# SPI_IFC.net
KiCad netlist of a schematic drawn in Altium Designer
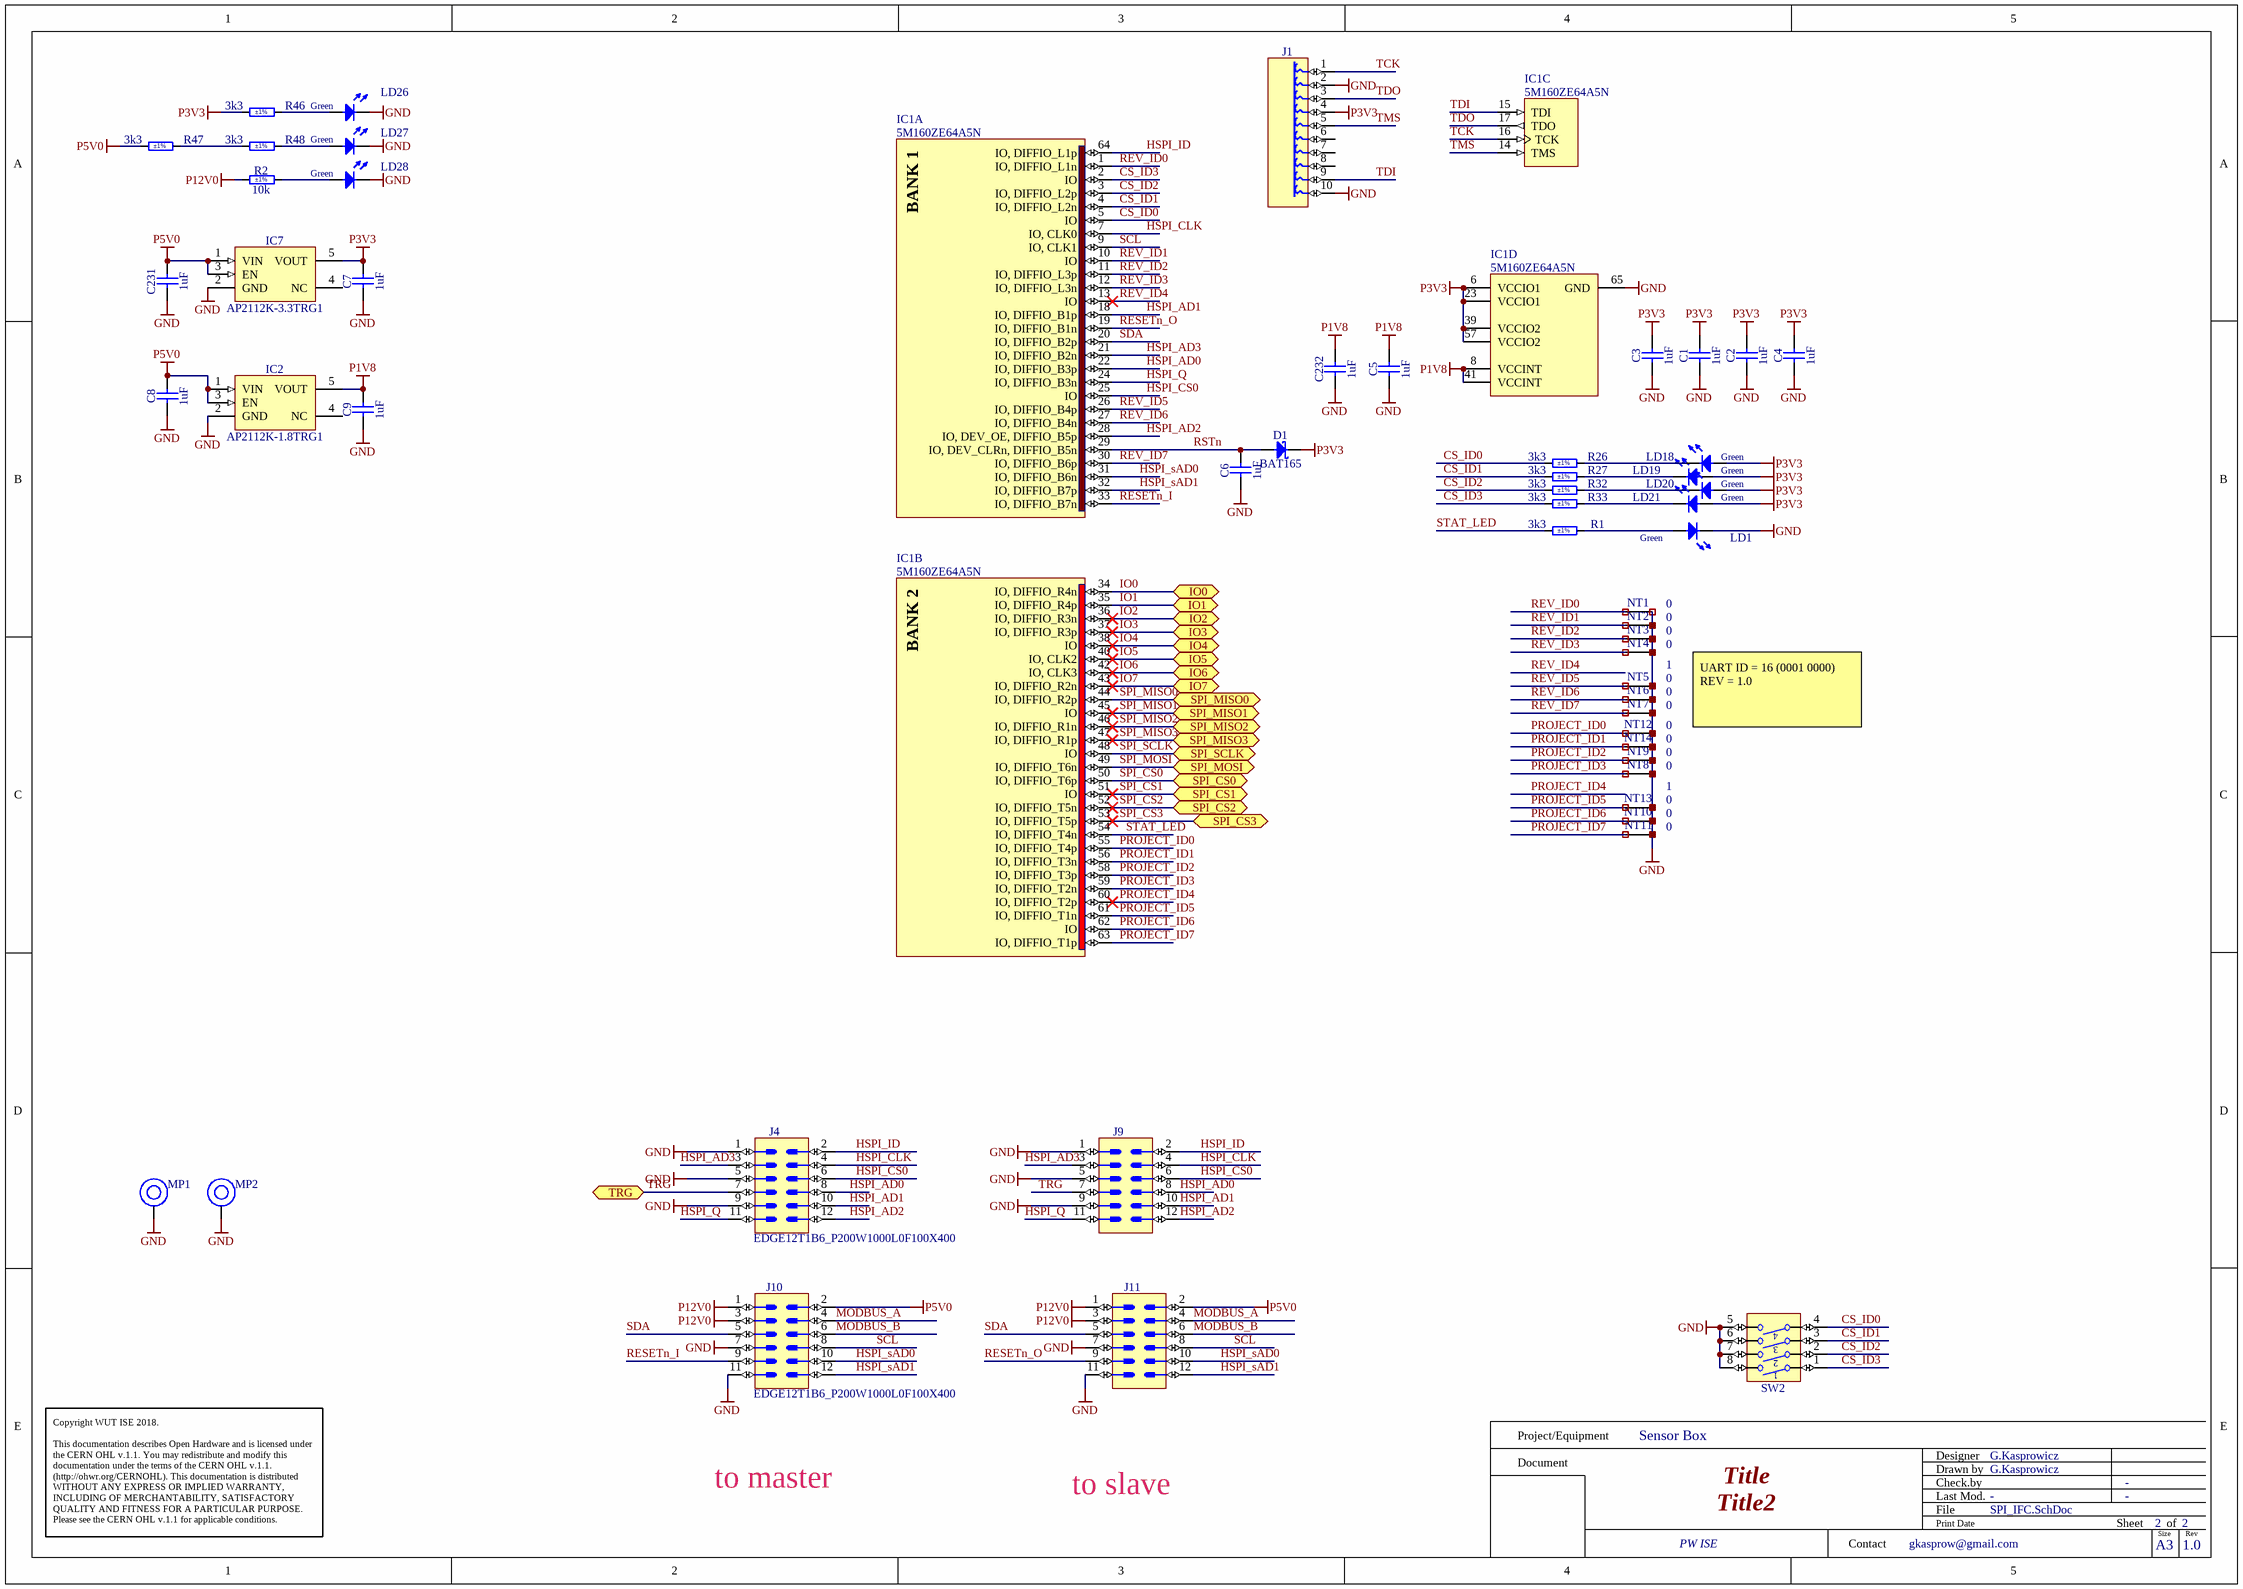
[diagram p0: SPI_IFC.SchDoc]

(export (version "E")
  (design (tool "Eeschema 10.0.6"))
  (components
    (comp (ref "C1")
      (value "1uF")
      (footprint "CAPC1005X55N")
      (description "Non-polarised capacitor")
      (fields
        (field (name "PART NUMBER") "CC0402_1UF_16V_10%_X5R")
        (field (name "VOLTAGE") "16V")
        (field (name "AUTHOR") "CERN DEM JLC")
      )
      (libsource (lib "Capacitors") (part "Capacitor - non polarized"))
    )
    (comp (ref "C2")
      (value "1uF")
      (footprint "CAPC1005X55N")
      (description "Non-polarised capacitor")
      (fields
        (field (name "PART NUMBER") "CC0402_1UF_16V_10%_X5R")
        (field (name "VOLTAGE") "16V")
        (field (name "AUTHOR") "CERN DEM JLC")
      )
      (libsource (lib "Capacitors") (part "Capacitor - non polarized"))
    )
    (comp (ref "C3")
      (value "1uF")
      (footprint "CAPC1005X55N")
      (description "Non-polarised capacitor")
      (fields
        (field (name "PART NUMBER") "CC0402_1UF_16V_10%_X5R")
        (field (name "VOLTAGE") "16V")
        (field (name "AUTHOR") "CERN DEM JLC")
      )
      (libsource (lib "Capacitors") (part "Capacitor - non polarized"))
    )
    (comp (ref "C4")
      (value "1uF")
      (footprint "CAPC1005X55N")
      (description "Non-polarised capacitor")
      (fields
        (field (name "PART NUMBER") "CC0402_1UF_16V_10%_X5R")
        (field (name "VOLTAGE") "16V")
        (field (name "AUTHOR") "CERN DEM JLC")
      )
      (libsource (lib "Capacitors") (part "Capacitor - non polarized"))
    )
    (comp (ref "C5")
      (value "1uF")
      (footprint "CAPC1005X55N")
      (description "Non-polarised capacitor")
      (fields
        (field (name "PART NUMBER") "CC0402_1UF_16V_10%_X5R")
        (field (name "VOLTAGE") "16V")
        (field (name "AUTHOR") "CERN DEM JLC")
      )
      (libsource (lib "Capacitors") (part "Capacitor - non polarized"))
    )
    (comp (ref "C6")
      (value "1uF")
      (footprint "CAPC1005X55N")
      (description "Non-polarised capacitor")
      (fields
        (field (name "PART NUMBER") "CC0402_1UF_16V_10%_X5R")
        (field (name "VOLTAGE") "16V")
        (field (name "AUTHOR") "CERN DEM JLC")
      )
      (libsource (lib "Capacitors") (part "Capacitor - non polarized"))
    )
    (comp (ref "C7")
      (value "1uF")
      (footprint "CAPC1005X55N")
      (description "Non-polarised capacitor")
      (fields
        (field (name "PART NUMBER") "CC0402_1UF_16V_10%_X5R")
        (field (name "VOLTAGE") "16V")
        (field (name "AUTHOR") "CERN DEM JLC")
      )
      (libsource (lib "Capacitors") (part "Capacitor - non polarized"))
    )
    (comp (ref "C8")
      (value "1uF")
      (footprint "CAPC1005X55N")
      (description "Non-polarised capacitor")
      (fields
        (field (name "PART NUMBER") "CC0402_1UF_16V_10%_X5R")
        (field (name "VOLTAGE") "16V")
        (field (name "AUTHOR") "CERN DEM JLC")
      )
      (libsource (lib "Capacitors") (part "Capacitor - non polarized"))
    )
    (comp (ref "C9")
      (value "1uF")
      (footprint "CAPC1005X55N")
      (description "Non-polarised capacitor")
      (fields
        (field (name "PART NUMBER") "CC0402_1UF_16V_10%_X5R")
        (field (name "VOLTAGE") "16V")
        (field (name "AUTHOR") "CERN DEM JLC")
      )
      (libsource (lib "Capacitors") (part "Capacitor - non polarized"))
    )
    (comp (ref "C231")
      (value "1uF")
      (footprint "CAPC1005X55N")
      (description "Non-polarised capacitor")
      (fields
        (field (name "PART NUMBER") "CC0402_1UF_16V_10%_X5R")
        (field (name "VOLTAGE") "16V")
        (field (name "AUTHOR") "CERN DEM JLC")
      )
      (libsource (lib "Capacitors") (part "Capacitor - non polarized"))
    )
    (comp (ref "C232")
      (value "1uF")
      (footprint "CAPC1005X55N")
      (description "Non-polarised capacitor")
      (fields
        (field (name "PART NUMBER") "CC0402_1UF_16V_10%_X5R")
        (field (name "VOLTAGE") "16V")
        (field (name "AUTHOR") "CERN DEM JLC")
      )
      (libsource (lib "Capacitors") (part "Capacitor - non polarized"))
    )
    (comp (ref "D1")
      (value "BAT165")
      (footprint "SOD2512X110N")
      (description "Schottky Diode")
      (fields
        (field (name "VOLTAGE") "40V")
        (field (name "POWER") "750mA")
        (field (name "AUTHOR") "CERN DEM JLC")
      )
      (libsource (lib "ICs And Semiconductors") (part "Diode Schottky"))
    )
    (comp (ref "IC1")
      (value "5M160ZE64A5N")
      (footprint "QFP40P900X900X120-65N-S550")
      (fields (field (name "MANUFACTURER") "ALTERA") (field (name "AUTHOR") "CERN DEM JLC"))
      (libsource (lib "ICs And Semiconductors") (part "5M160ZE64A5N"))
    )
    (comp (ref "IC2")
      (value "AP2112K-1.8TRG1")
      (footprint "SOT95P285X140-5N")
      (description "600mA CMOS Low Dropout Linear Regulator with Enable")
      (fields
        (field (name "MANUFACTURER") "DIODES INCORPORATED")
        (field (name "MANUFACTURER PART NUMBER") "AP2112K-1.8")
        (field (name "AUTHOR") "CERN DEM JLC")
      )
      (libsource (lib "ICs And Semiconductors") (part "AP2112K"))
    )
    (comp (ref "IC7")
      (value "AP2112K-3.3TRG1")
      (footprint "SOT95P285X140-5N")
      (description "600mA CMOS Low Dropout Linear Regulator with Enable")
      (fields
        (field (name "MANUFACTURER") "DIODES INCORPORATED")
        (field (name "MANUFACTURER PART NUMBER") "AP2112K-3.3")
        (field (name "AUTHOR") "CERN DEM MR")
      )
      (libsource (lib "ICs And Semiconductors") (part "AP2112K"))
    )
    (comp (ref "J1")
      (value "TC2050-IDC")
      (footprint "TC2050-IDC")
      (description "TC2030-MCP and TC2050-IDC Pad Contact")
      (fields (field (name "AUTHOR") "CERN DEM HF"))
      (libsource (lib "Eletro-mechanical") (part "TC2050-IDC"))
    )
    (comp (ref "J4")
      (value "~")
      (footprint "EDGE12T1B6_P200W1000L0F100X400")
      (description "PCB Edge Connector 12 (2x6)")
      (fields
        (field (name "PART NUMBER") "EDGE10T1B6_P200W1000L0F100X400")
        (field (name "AUTHOR") "CERN DEM MR")
      )
      (libsource (lib "Connectors") (part "PCB Edge Connector 12 (2x6)"))
    )
    (comp (ref "J9")
      (value "~")
      (footprint "EDGE12T5B10_P200W1000L0F100X400")
      (description "PCB Edge Connector 12 (2x6)")
      (fields (field (name "PART NUMBER") "EDGE12T5B10_P200W1000L0F100X400") (field (name "AUTHOR") "GK"))
      (libsource (lib "Connectors") (part "PCB Edge Connector 12 (2x6) R"))
    )
    (comp (ref "J10")
      (value "~")
      (footprint "EDGE12T1B6_P200W1000L0F100X400")
      (description "PCB Edge Connector 12 (2x6)")
      (fields
        (field (name "PART NUMBER") "EDGE10T1B6_P200W1000L0F100X400")
        (field (name "AUTHOR") "CERN DEM MR")
      )
      (libsource (lib "Connectors") (part "PCB Edge Connector 12 (2x6)"))
    )
    (comp (ref "J11")
      (value "~")
      (footprint "EDGE12T5B10_P200W1000L0F100X400")
      (description "PCB Edge Connector 12 (2x6)")
      (fields (field (name "PART NUMBER") "EDGE12T5B10_P200W1000L0F100X400") (field (name "AUTHOR") "GK"))
      (libsource (lib "Connectors") (part "PCB Edge Connector 12 (2x6) R"))
    )
    (comp (ref "LD1")
      (value "Green")
      (footprint "LED_KINGBRIGHT_KP-1608CGCK")
      (description "LED Green 1C 2A")
      (fields
        (field (name "PART NUMBER") "LED_KINGBRIGHT_KP-1608CGCK")
        (field (name "MANUFACTURER") "KINGBRIGHT")
        (field (name "AUTHOR") "CERN DEM HF")
      )
      (libsource (lib "ICs And Semiconductors") (part "LED Green 1C 2A"))
    )
    (comp (ref "LD18")
      (value "Green")
      (footprint "LED_KINGBRIGHT_KP-1608CGCK")
      (description "LED Green 1C 2A")
      (fields
        (field (name "PART NUMBER") "LED_KINGBRIGHT_KP-1608CGCK")
        (field (name "MANUFACTURER") "KINGBRIGHT")
        (field (name "AUTHOR") "CERN DEM HF")
      )
      (libsource (lib "ICs And Semiconductors") (part "LED Green 1C 2A"))
    )
    (comp (ref "LD19")
      (value "Green")
      (footprint "LED_KINGBRIGHT_KP-1608CGCK")
      (description "LED Green 1C 2A")
      (fields
        (field (name "PART NUMBER") "LED_KINGBRIGHT_KP-1608CGCK")
        (field (name "MANUFACTURER") "KINGBRIGHT")
        (field (name "AUTHOR") "CERN DEM HF")
      )
      (libsource (lib "ICs And Semiconductors") (part "LED Green 1C 2A"))
    )
    (comp (ref "LD20")
      (value "Green")
      (footprint "LED_KINGBRIGHT_KP-1608CGCK")
      (description "LED Green 1C 2A")
      (fields
        (field (name "PART NUMBER") "LED_KINGBRIGHT_KP-1608CGCK")
        (field (name "MANUFACTURER") "KINGBRIGHT")
        (field (name "AUTHOR") "CERN DEM HF")
      )
      (libsource (lib "ICs And Semiconductors") (part "LED Green 1C 2A"))
    )
    (comp (ref "LD21")
      (value "Green")
      (footprint "LED_KINGBRIGHT_KP-1608CGCK")
      (description "LED Green 1C 2A")
      (fields
        (field (name "PART NUMBER") "LED_KINGBRIGHT_KP-1608CGCK")
        (field (name "MANUFACTURER") "KINGBRIGHT")
        (field (name "AUTHOR") "CERN DEM HF")
      )
      (libsource (lib "ICs And Semiconductors") (part "LED Green 1C 2A"))
    )
    (comp (ref "LD26")
      (value "Green")
      (footprint "LED_KINGBRIGHT_KP-1608CGCK")
      (description "LED Green 1C 2A")
      (fields
        (field (name "PART NUMBER") "LED_KINGBRIGHT_KP-1608CGCK")
        (field (name "MANUFACTURER") "KINGBRIGHT")
        (field (name "AUTHOR") "CERN DEM HF")
      )
      (libsource (lib "ICs And Semiconductors") (part "LED Green 1C 2A"))
    )
    (comp (ref "LD27")
      (value "Green")
      (footprint "LED_KINGBRIGHT_KP-1608CGCK")
      (description "LED Green 1C 2A")
      (fields
        (field (name "PART NUMBER") "LED_KINGBRIGHT_KP-1608CGCK")
        (field (name "MANUFACTURER") "KINGBRIGHT")
        (field (name "AUTHOR") "CERN DEM HF")
      )
      (libsource (lib "ICs And Semiconductors") (part "LED Green 1C 2A"))
    )
    (comp (ref "LD28")
      (value "Green")
      (footprint "LED_KINGBRIGHT_KP-1608CGCK")
      (description "LED Green 1C 2A")
      (fields
        (field (name "PART NUMBER") "LED_KINGBRIGHT_KP-1608CGCK")
        (field (name "MANUFACTURER") "KINGBRIGHT")
        (field (name "AUTHOR") "CERN DEM HF")
      )
      (libsource (lib "ICs And Semiconductors") (part "LED Green 1C 2A"))
    )
    (comp (ref "MP1")
      (value "M1.6 x 3mm")
      (footprint "97730306330")
      (description "WA-SMSI SMT Steel Spacer with internal Thread Bottom closed, OD 3.3mm, M1.6 x 3mm")
      (fields
        (field (name "MANUFACTURER PART NUMBER") "97730306330R")
        (field (name "MANUFACTURER") "Wurth Elektronik")
      )
      (libsource (lib "Altium_WA-SMSI (rev22a)") (part "97730306330R"))
    )
    (comp (ref "MP2")
      (value "M1.6 x 3mm")
      (footprint "97730306330")
      (description "WA-SMSI SMT Steel Spacer with internal Thread Bottom closed, OD 3.3mm, M1.6 x 3mm")
      (fields
        (field (name "MANUFACTURER PART NUMBER") "97730306330R")
        (field (name "MANUFACTURER") "Wurth Elektronik")
      )
      (libsource (lib "Altium_WA-SMSI (rev22a)") (part "97730306330R"))
    )
    (comp (ref "NT1")
      (value "Net Tie")
      (footprint "Net Tie 3")
      (fields (field (name "PART NUMBER") "Net Tie 3") (field (name "AUTHOR") "CERN DEM HF"))
      (libsource (lib "Eletro-mechanical") (part "Net Tie_a"))
    )
    (comp (ref "NT2")
      (value "Net Tie")
      (footprint "Net Tie 3")
      (fields (field (name "PART NUMBER") "Net Tie 3") (field (name "AUTHOR") "CERN DEM HF"))
      (libsource (lib "Eletro-mechanical") (part "Net Tie_a"))
    )
    (comp (ref "NT3")
      (value "Net Tie")
      (footprint "Net Tie 3")
      (fields (field (name "PART NUMBER") "Net Tie 3") (field (name "AUTHOR") "CERN DEM HF"))
      (libsource (lib "Eletro-mechanical") (part "Net Tie_a"))
    )
    (comp (ref "NT4")
      (value "Net Tie")
      (footprint "Net Tie 3")
      (fields (field (name "PART NUMBER") "Net Tie 3") (field (name "AUTHOR") "CERN DEM HF"))
      (libsource (lib "Eletro-mechanical") (part "Net Tie_a"))
    )
    (comp (ref "NT5")
      (value "Net Tie")
      (footprint "Net Tie 3")
      (fields (field (name "PART NUMBER") "Net Tie 3") (field (name "AUTHOR") "CERN DEM HF"))
      (libsource (lib "Eletro-mechanical") (part "Net Tie_a"))
    )
    (comp (ref "NT6")
      (value "Net Tie")
      (footprint "Net Tie 3")
      (fields (field (name "PART NUMBER") "Net Tie 3") (field (name "AUTHOR") "CERN DEM HF"))
      (libsource (lib "Eletro-mechanical") (part "Net Tie_a"))
    )
    (comp (ref "NT7")
      (value "Net Tie")
      (footprint "Net Tie 3")
      (fields (field (name "PART NUMBER") "Net Tie 3") (field (name "AUTHOR") "CERN DEM HF"))
      (libsource (lib "Eletro-mechanical") (part "Net Tie_a"))
    )
    (comp (ref "NT8")
      (value "Net Tie")
      (footprint "Net Tie 3")
      (fields (field (name "PART NUMBER") "Net Tie 3") (field (name "AUTHOR") "CERN DEM HF"))
      (libsource (lib "Eletro-mechanical") (part "Net Tie_a"))
    )
    (comp (ref "NT9")
      (value "Net Tie")
      (footprint "Net Tie 3")
      (fields (field (name "PART NUMBER") "Net Tie 3") (field (name "AUTHOR") "CERN DEM HF"))
      (libsource (lib "Eletro-mechanical") (part "Net Tie_a"))
    )
    (comp (ref "NT10")
      (value "Net Tie")
      (footprint "Net Tie 3")
      (fields (field (name "PART NUMBER") "Net Tie 3") (field (name "AUTHOR") "CERN DEM HF"))
      (libsource (lib "Eletro-mechanical") (part "Net Tie_a"))
    )
    (comp (ref "NT11")
      (value "Net Tie")
      (footprint "Net Tie 3")
      (fields (field (name "PART NUMBER") "Net Tie 3") (field (name "AUTHOR") "CERN DEM HF"))
      (libsource (lib "Eletro-mechanical") (part "Net Tie_a"))
    )
    (comp (ref "NT12")
      (value "Net Tie")
      (footprint "Net Tie 3")
      (fields (field (name "PART NUMBER") "Net Tie 3") (field (name "AUTHOR") "CERN DEM HF"))
      (libsource (lib "Eletro-mechanical") (part "Net Tie_a"))
    )
    (comp (ref "NT13")
      (value "Net Tie")
      (footprint "Net Tie 3")
      (fields (field (name "PART NUMBER") "Net Tie 3") (field (name "AUTHOR") "CERN DEM HF"))
      (libsource (lib "Eletro-mechanical") (part "Net Tie_a"))
    )
    (comp (ref "NT14")
      (value "Net Tie")
      (footprint "Net Tie 3")
      (fields (field (name "PART NUMBER") "Net Tie 3") (field (name "AUTHOR") "CERN DEM HF"))
      (libsource (lib "Eletro-mechanical") (part "Net Tie_a"))
    )
    (comp (ref "R1")
      (value "3k3")
      (footprint "RESC1005X40N")
      (description "Resistor - 1%")
      (fields
        (field (name "TOLERANCE") "±1%")
        (field (name "PART NUMBER") "R0402_3K3_1%_0.0625W_100PPM")
        (field (name "POWER") "0.0625W")
        (field (name "AUTHOR") "CERN DEM JLC")
      )
      (libsource (lib "Resistors") (part "Resistor - 1%"))
    )
    (comp (ref "R2")
      (value "10k")
      (footprint "RESC1005X40N")
      (description "Resistor - 1%")
      (fields
        (field (name "TOLERANCE") "±1%")
        (field (name "PART NUMBER") "R0402_10K_1%_0.0625W_100PPM")
        (field (name "POWER") "0.0625W")
        (field (name "AUTHOR") "CERN DEM JLC")
      )
      (libsource (lib "Resistors") (part "Resistor - 1%"))
    )
    (comp (ref "R26")
      (value "3k3")
      (footprint "RESC1005X40N")
      (description "Resistor - 1%")
      (fields
        (field (name "TOLERANCE") "±1%")
        (field (name "PART NUMBER") "R0402_3K3_1%_0.0625W_100PPM")
        (field (name "POWER") "0.0625W")
        (field (name "AUTHOR") "CERN DEM JLC")
      )
      (libsource (lib "Resistors") (part "Resistor - 1%"))
    )
    (comp (ref "R27")
      (value "3k3")
      (footprint "RESC1005X40N")
      (description "Resistor - 1%")
      (fields
        (field (name "TOLERANCE") "±1%")
        (field (name "PART NUMBER") "R0402_3K3_1%_0.0625W_100PPM")
        (field (name "POWER") "0.0625W")
        (field (name "AUTHOR") "CERN DEM JLC")
      )
      (libsource (lib "Resistors") (part "Resistor - 1%"))
    )
    (comp (ref "R32")
      (value "3k3")
      (footprint "RESC1005X40N")
      (description "Resistor - 1%")
      (fields
        (field (name "TOLERANCE") "±1%")
        (field (name "PART NUMBER") "R0402_3K3_1%_0.0625W_100PPM")
        (field (name "POWER") "0.0625W")
        (field (name "AUTHOR") "CERN DEM JLC")
      )
      (libsource (lib "Resistors") (part "Resistor - 1%"))
    )
    (comp (ref "R33")
      (value "3k3")
      (footprint "RESC1005X40N")
      (description "Resistor - 1%")
      (fields
        (field (name "TOLERANCE") "±1%")
        (field (name "PART NUMBER") "R0402_3K3_1%_0.0625W_100PPM")
        (field (name "POWER") "0.0625W")
        (field (name "AUTHOR") "CERN DEM JLC")
      )
      (libsource (lib "Resistors") (part "Resistor - 1%"))
    )
    (comp (ref "R46")
      (value "3k3")
      (footprint "RESC1005X40N")
      (description "Resistor - 1%")
      (fields
        (field (name "TOLERANCE") "±1%")
        (field (name "PART NUMBER") "R0402_3K3_1%_0.0625W_100PPM")
        (field (name "POWER") "0.0625W")
        (field (name "AUTHOR") "CERN DEM JLC")
      )
      (libsource (lib "Resistors") (part "Resistor - 1%"))
    )
    (comp (ref "R47")
      (value "3k3")
      (footprint "RESC1005X40N")
      (description "Resistor - 1%")
      (fields
        (field (name "TOLERANCE") "±1%")
        (field (name "PART NUMBER") "R0402_3K3_1%_0.0625W_100PPM")
        (field (name "POWER") "0.0625W")
        (field (name "AUTHOR") "CERN DEM JLC")
      )
      (libsource (lib "Resistors") (part "Resistor - 1%"))
    )
    (comp (ref "R48")
      (value "3k3")
      (footprint "RESC1005X40N")
      (description "Resistor - 1%")
      (fields
        (field (name "TOLERANCE") "±1%")
        (field (name "PART NUMBER") "R0402_3K3_1%_0.0625W_100PPM")
        (field (name "POWER") "0.0625W")
        (field (name "AUTHOR") "CERN DEM JLC")
      )
      (libsource (lib "Resistors") (part "Resistor - 1%"))
    )
    (comp (ref "SW2")
      (value "Switch")
      (footprint "SW_OMRON_A6H-4102")
      (description "4 Ways SPST DIP Switch")
      (fields
        (field (name "PART NUMBER") "SW_OMRON_A6H-4102")
        (field (name "MANUFACTURER") "OMRON")
        (field (name "AUTHOR") "CERN DEM JLC")
      )
      (libsource (lib "Eletro-mechanical") (part "SW 4x SPST DIP Switch"))
    )
  )
  (nets
    (net (code "1") (name "/CS_ID0") (class "Default")
      (node (ref "IC1") (pin "5") (pinfunction "IO_5") (pintype "bidirectional"))
      (node (ref "R26") (pin "2") (pinfunction "2_2") (pintype "passive"))
      (node (ref "SW2") (pin "4") (pinfunction "4_4") (pintype "bidirectional"))
    )
    (net (code "2") (name "/CS_ID1") (class "Default")
      (node (ref "IC1") (pin "4") (pinfunction "IO,_DIFFIO_L2n_4") (pintype "bidirectional"))
      (node (ref "R27") (pin "2") (pinfunction "2_2") (pintype "passive"))
      (node (ref "SW2") (pin "3") (pinfunction "3_3") (pintype "bidirectional"))
    )
    (net (code "3") (name "/CS_ID2") (class "Default")
      (node (ref "IC1") (pin "3") (pinfunction "IO,_DIFFIO_L2p_3") (pintype "bidirectional"))
      (node (ref "R32") (pin "2") (pinfunction "2_2") (pintype "passive"))
      (node (ref "SW2") (pin "2") (pinfunction "2_2") (pintype "bidirectional"))
    )
    (net (code "4") (name "/CS_ID3") (class "Default")
      (node (ref "IC1") (pin "2") (pinfunction "IO_2") (pintype "bidirectional"))
      (node (ref "R33") (pin "2") (pinfunction "2_2") (pintype "passive"))
      (node (ref "SW2") (pin "1") (pinfunction "1_1") (pintype "bidirectional"))
    )
    (net (code "5") (name "/HSPI_AD0") (class "Default")
      (node (ref "IC1") (pin "22") (pinfunction "IO,_DIFFIO_B3p_22") (pintype "bidirectional"))
      (node (ref "J4") (pin "8") (pinfunction "8_8") (pintype "bidirectional"))
      (node (ref "J9") (pin "8") (pinfunction "8_8") (pintype "bidirectional"))
    )
    (net (code "6") (name "/HSPI_AD1") (class "Default")
      (node (ref "IC1") (pin "18") (pinfunction "IO,_DIFFIO_B1p_18") (pintype "bidirectional"))
      (node (ref "J4") (pin "10") (pinfunction "10_10") (pintype "bidirectional"))
      (node (ref "J9") (pin "10") (pinfunction "10_10") (pintype "bidirectional"))
    )
    (net (code "7") (name "/HSPI_AD2") (class "Default")
      (node (ref "IC1") (pin "28") (pinfunction "IO,_DEV_OE,_DIFFIO_B5p_28") (pintype "bidirectional"))
      (node (ref "J4") (pin "12") (pinfunction "12_12") (pintype "bidirectional"))
      (node (ref "J9") (pin "12") (pinfunction "12_12") (pintype "bidirectional"))
    )
    (net (code "8") (name "/HSPI_AD3") (class "Default")
      (node (ref "IC1") (pin "21") (pinfunction "IO,_DIFFIO_B2n_21") (pintype "bidirectional"))
      (node (ref "J4") (pin "3") (pinfunction "3_3") (pintype "bidirectional"))
      (node (ref "J9") (pin "3") (pinfunction "3_3") (pintype "bidirectional"))
    )
    (net (code "9") (name "/HSPI_CLK") (class "Default")
      (node (ref "IC1") (pin "7") (pinfunction "IO,_CLK0_7") (pintype "bidirectional"))
      (node (ref "J4") (pin "4") (pinfunction "4_4") (pintype "bidirectional"))
      (node (ref "J9") (pin "4") (pinfunction "4_4") (pintype "bidirectional"))
    )
    (net (code "10") (name "/HSPI_CS0") (class "Default")
      (node (ref "IC1") (pin "25") (pinfunction "IO_25") (pintype "bidirectional"))
      (node (ref "J4") (pin "6") (pinfunction "6_6") (pintype "bidirectional"))
      (node (ref "J9") (pin "6") (pinfunction "6_6") (pintype "bidirectional"))
    )
    (net (code "11") (name "/HSPI_ID") (class "Default")
      (node (ref "IC1") (pin "64") (pinfunction "IO,_DIFFIO_L1p_64") (pintype "bidirectional"))
      (node (ref "J4") (pin "2") (pinfunction "2_2") (pintype "bidirectional"))
      (node (ref "J9") (pin "2") (pinfunction "2_2") (pintype "bidirectional"))
    )
    (net (code "12") (name "/HSPI_Q") (class "Default")
      (node (ref "IC1") (pin "24") (pinfunction "IO,_DIFFIO_B3n_24") (pintype "bidirectional"))
      (node (ref "J4") (pin "11") (pinfunction "11_11") (pintype "bidirectional"))
      (node (ref "J9") (pin "11") (pinfunction "11_11") (pintype "bidirectional"))
    )
    (net (code "13") (name "/HSPI_sAD0") (class "Default")
      (node (ref "IC1") (pin "31") (pinfunction "IO,_DIFFIO_B6n_31") (pintype "bidirectional"))
      (node (ref "J10") (pin "10") (pinfunction "10_10") (pintype "bidirectional"))
      (node (ref "J11") (pin "10") (pinfunction "10_10") (pintype "bidirectional"))
    )
    (net (code "14") (name "/HSPI_sAD1") (class "Default")
      (node (ref "IC1") (pin "32") (pinfunction "IO,_DIFFIO_B7p_32") (pintype "bidirectional"))
      (node (ref "J10") (pin "12") (pinfunction "12_12") (pintype "bidirectional"))
      (node (ref "J11") (pin "12") (pinfunction "12_12") (pintype "bidirectional"))
    )
    (net (code "15") (name "/IO0") (class "Default")
      (node (ref "IC1") (pin "34") (pinfunction "IO,_DIFFIO_R4n_34") (pintype "bidirectional"))
    )
    (net (code "16") (name "/IO1") (class "Default")
      (node (ref "IC1") (pin "35") (pinfunction "IO,_DIFFIO_R4p_35") (pintype "bidirectional"))
    )
    (net (code "17") (name "/IO2") (class "Default")
      (node (ref "IC1") (pin "36") (pinfunction "IO,_DIFFIO_R3n_36") (pintype "bidirectional+no_connect"))
    )
    (net (code "18") (name "/IO3") (class "Default")
      (node (ref "IC1") (pin "37") (pinfunction "IO,_DIFFIO_R3p_37") (pintype "bidirectional+no_connect"))
    )
    (net (code "19") (name "/IO4") (class "Default")
      (node (ref "IC1") (pin "38") (pinfunction "IO_38") (pintype "bidirectional+no_connect"))
    )
    (net (code "20") (name "/IO5") (class "Default")
      (node (ref "IC1") (pin "40") (pinfunction "IO,_CLK2_40") (pintype "bidirectional+no_connect"))
    )
    (net (code "21") (name "/IO6") (class "Default")
      (node (ref "IC1") (pin "42") (pinfunction "IO,_CLK3_42") (pintype "bidirectional+no_connect"))
    )
    (net (code "22") (name "/IO7") (class "Default")
      (node (ref "IC1") (pin "43") (pinfunction "IO,_DIFFIO_R2n_43") (pintype "bidirectional+no_connect"))
    )
    (net (code "23") (name "/MODBUS_A") (class "Default")
      (node (ref "J10") (pin "4") (pinfunction "4_4") (pintype "bidirectional"))
      (node (ref "J11") (pin "4") (pinfunction "4_4") (pintype "bidirectional"))
    )
    (net (code "24") (name "/MODBUS_B") (class "Default")
      (node (ref "J10") (pin "6") (pinfunction "6_6") (pintype "bidirectional"))
      (node (ref "J11") (pin "6") (pinfunction "6_6") (pintype "bidirectional"))
    )
    (net (code "25") (name "/PROJECT_ID0") (class "Default")
      (node (ref "IC1") (pin "55") (pinfunction "IO,_DIFFIO_T4p_55") (pintype "bidirectional"))
      (node (ref "NT12") (pin "1") (pinfunction "1_1") (pintype "bidirectional"))
    )
    (net (code "26") (name "/PROJECT_ID1") (class "Default")
      (node (ref "IC1") (pin "56") (pinfunction "IO,_DIFFIO_T3n_56") (pintype "bidirectional"))
      (node (ref "NT14") (pin "1") (pinfunction "1_1") (pintype "bidirectional"))
    )
    (net (code "27") (name "/PROJECT_ID2") (class "Default")
      (node (ref "IC1") (pin "58") (pinfunction "IO,_DIFFIO_T3p_58") (pintype "bidirectional"))
      (node (ref "NT9") (pin "1") (pinfunction "1_1") (pintype "bidirectional"))
    )
    (net (code "28") (name "/PROJECT_ID3") (class "Default")
      (node (ref "IC1") (pin "59") (pinfunction "IO,_DIFFIO_T2n_59") (pintype "bidirectional"))
      (node (ref "NT8") (pin "1") (pinfunction "1_1") (pintype "bidirectional"))
    )
    (net (code "29") (name "/PROJECT_ID4") (class "Default")
      (node (ref "IC1") (pin "60") (pinfunction "IO,_DIFFIO_T2p_60") (pintype "bidirectional"))
    )
    (net (code "30") (name "/PROJECT_ID5") (class "Default")
      (node (ref "IC1") (pin "61") (pinfunction "IO,_DIFFIO_T1n_61") (pintype "bidirectional"))
      (node (ref "NT13") (pin "1") (pinfunction "1_1") (pintype "bidirectional"))
    )
    (net (code "31") (name "/PROJECT_ID6") (class "Default")
      (node (ref "IC1") (pin "62") (pinfunction "IO_62") (pintype "bidirectional"))
      (node (ref "NT10") (pin "1") (pinfunction "1_1") (pintype "bidirectional"))
    )
    (net (code "32") (name "/PROJECT_ID7") (class "Default")
      (node (ref "IC1") (pin "63") (pinfunction "IO,_DIFFIO_T1p_63") (pintype "bidirectional"))
      (node (ref "NT11") (pin "1") (pinfunction "1_1") (pintype "bidirectional"))
    )
    (net (code "33") (name "/RESETn_I") (class "Default")
      (node (ref "IC1") (pin "33") (pinfunction "IO,_DIFFIO_B7n_33") (pintype "bidirectional"))
      (node (ref "J10") (pin "9") (pinfunction "9_9") (pintype "bidirectional"))
    )
    (net (code "34") (name "/RESETn_O") (class "Default")
      (node (ref "IC1") (pin "19") (pinfunction "IO,_DIFFIO_B1n_19") (pintype "bidirectional"))
      (node (ref "J11") (pin "9") (pinfunction "9_9") (pintype "bidirectional"))
    )
    (net (code "35") (name "/REV_ID0") (class "Default")
      (node (ref "IC1") (pin "1") (pinfunction "IO,_DIFFIO_L1n_1") (pintype "bidirectional"))
      (node (ref "NT1") (pin "1") (pinfunction "1_1") (pintype "bidirectional"))
    )
    (net (code "36") (name "/REV_ID1") (class "Default")
      (node (ref "IC1") (pin "10") (pinfunction "IO_10") (pintype "bidirectional"))
      (node (ref "NT2") (pin "1") (pinfunction "1_1") (pintype "bidirectional"))
    )
    (net (code "37") (name "/REV_ID2") (class "Default")
      (node (ref "IC1") (pin "11") (pinfunction "IO,_DIFFIO_L3p_11") (pintype "bidirectional"))
      (node (ref "NT3") (pin "1") (pinfunction "1_1") (pintype "bidirectional"))
    )
    (net (code "38") (name "/REV_ID3") (class "Default")
      (node (ref "IC1") (pin "12") (pinfunction "IO,_DIFFIO_L3n_12") (pintype "bidirectional"))
      (node (ref "NT4") (pin "1") (pinfunction "1_1") (pintype "bidirectional"))
    )
    (net (code "39") (name "/REV_ID4") (class "Default")
      (node (ref "IC1") (pin "13") (pinfunction "IO_13") (pintype "bidirectional+no_connect"))
    )
    (net (code "40") (name "/REV_ID5") (class "Default")
      (node (ref "IC1") (pin "26") (pinfunction "IO,_DIFFIO_B4p_26") (pintype "bidirectional"))
      (node (ref "NT5") (pin "1") (pinfunction "1_1") (pintype "bidirectional"))
    )
    (net (code "41") (name "/REV_ID6") (class "Default")
      (node (ref "IC1") (pin "27") (pinfunction "IO,_DIFFIO_B4n_27") (pintype "bidirectional"))
      (node (ref "NT6") (pin "1") (pinfunction "1_1") (pintype "bidirectional"))
    )
    (net (code "42") (name "/REV_ID7") (class "Default")
      (node (ref "IC1") (pin "30") (pinfunction "IO,_DIFFIO_B6p_30") (pintype "bidirectional"))
      (node (ref "NT7") (pin "1") (pinfunction "1_1") (pintype "bidirectional"))
    )
    (net (code "43") (name "/RSTn") (class "Default")
      (node (ref "C6") (pin "2") (pinfunction "2_2") (pintype "passive"))
      (node (ref "D1") (pin "2") (pinfunction "A_2") (pintype "passive"))
      (node (ref "IC1") (pin "29") (pinfunction "IO,_DEV_CLRn,_DIFFIO_B5n_29") (pintype "bidirectional"))
    )
    (net (code "44") (name "/SCL") (class "Default")
      (node (ref "IC1") (pin "9") (pinfunction "IO,_CLK1_9") (pintype "bidirectional"))
      (node (ref "J10") (pin "8") (pinfunction "8_8") (pintype "bidirectional"))
      (node (ref "J11") (pin "8") (pinfunction "8_8") (pintype "bidirectional"))
    )
    (net (code "45") (name "/SDA") (class "Default")
      (node (ref "IC1") (pin "20") (pinfunction "IO,_DIFFIO_B2p_20") (pintype "bidirectional"))
      (node (ref "J10") (pin "5") (pinfunction "5_5") (pintype "bidirectional"))
      (node (ref "J11") (pin "5") (pinfunction "5_5") (pintype "bidirectional"))
    )
    (net (code "46") (name "/SPI_CS0") (class "Default")
      (node (ref "IC1") (pin "50") (pinfunction "IO,_DIFFIO_T6p_50") (pintype "bidirectional"))
    )
    (net (code "47") (name "/SPI_CS1") (class "Default")
      (node (ref "IC1") (pin "51") (pinfunction "IO_51") (pintype "bidirectional+no_connect"))
    )
    (net (code "48") (name "/SPI_CS2") (class "Default")
      (node (ref "IC1") (pin "52") (pinfunction "IO,_DIFFIO_T5n_52") (pintype "bidirectional+no_connect"))
    )
    (net (code "49") (name "/SPI_CS3") (class "Default")
      (node (ref "IC1") (pin "53") (pinfunction "IO,_DIFFIO_T5p_53") (pintype "bidirectional+no_connect"))
    )
    (net (code "50") (name "/SPI_MISO0") (class "Default")
      (node (ref "IC1") (pin "44") (pinfunction "IO,_DIFFIO_R2p_44") (pintype "bidirectional"))
    )
    (net (code "51") (name "/SPI_MISO1") (class "Default")
      (node (ref "IC1") (pin "45") (pinfunction "IO_45") (pintype "bidirectional+no_connect"))
    )
    (net (code "52") (name "/SPI_MISO2") (class "Default")
      (node (ref "IC1") (pin "46") (pinfunction "IO,_DIFFIO_R1n_46") (pintype "bidirectional+no_connect"))
    )
    (net (code "53") (name "/SPI_MISO3") (class "Default")
      (node (ref "IC1") (pin "47") (pinfunction "IO,_DIFFIO_R1p_47") (pintype "bidirectional+no_connect"))
    )
    (net (code "54") (name "/SPI_MOSI") (class "Default")
      (node (ref "IC1") (pin "49") (pinfunction "IO,_DIFFIO_T6n_49") (pintype "bidirectional"))
    )
    (net (code "55") (name "/SPI_SCLK") (class "Default")
      (node (ref "IC1") (pin "48") (pinfunction "IO_48") (pintype "bidirectional"))
    )
    (net (code "56") (name "/STAT_LED") (class "Default")
      (node (ref "IC1") (pin "54") (pinfunction "IO,_DIFFIO_T4n_54") (pintype "bidirectional"))
      (node (ref "R1") (pin "2") (pinfunction "2_2") (pintype "passive"))
    )
    (net (code "57") (name "/TCK") (class "Default")
      (node (ref "IC1") (pin "16") (pinfunction "TCK_16") (pintype "input"))
      (node (ref "J1") (pin "1") (pinfunction "1_1") (pintype "bidirectional"))
    )
    (net (code "58") (name "/TDI") (class "Default")
      (node (ref "IC1") (pin "15") (pinfunction "TDI_15") (pintype "input"))
      (node (ref "J1") (pin "9") (pinfunction "9_9") (pintype "bidirectional"))
    )
    (net (code "59") (name "/TDO") (class "Default")
      (node (ref "IC1") (pin "17") (pinfunction "TDO_17") (pintype "output"))
      (node (ref "J1") (pin "3") (pinfunction "3_3") (pintype "bidirectional"))
    )
    (net (code "60") (name "/TMS") (class "Default")
      (node (ref "IC1") (pin "14") (pinfunction "TMS_14") (pintype "input"))
      (node (ref "J1") (pin "5") (pinfunction "5_5") (pintype "bidirectional"))
    )
    (net (code "61") (name "/TRG") (class "Default")
      (node (ref "J4") (pin "7") (pinfunction "7_7") (pintype "bidirectional"))
      (node (ref "J9") (pin "7") (pinfunction "7_7") (pintype "bidirectional"))
    )
    (net (code "62") (name "GND") (class "Default")
      (node (ref "C1") (pin "1") (pinfunction "1_1") (pintype "passive"))
      (node (ref "C2") (pin "1") (pinfunction "1_1") (pintype "passive"))
      (node (ref "C231") (pin "1") (pinfunction "1_1") (pintype "passive"))
      (node (ref "C232") (pin "1") (pinfunction "1_1") (pintype "passive"))
      (node (ref "C3") (pin "1") (pinfunction "1_1") (pintype "passive"))
      (node (ref "C4") (pin "1") (pinfunction "1_1") (pintype "passive"))
      (node (ref "C5") (pin "1") (pinfunction "1_1") (pintype "passive"))
      (node (ref "C6") (pin "1") (pinfunction "1_1") (pintype "passive"))
      (node (ref "C7") (pin "1") (pinfunction "1_1") (pintype "passive"))
      (node (ref "C8") (pin "1") (pinfunction "1_1") (pintype "passive"))
      (node (ref "C9") (pin "1") (pinfunction "1_1") (pintype "passive"))
      (node (ref "IC1") (pin "65") (pinfunction "GND_65") (pintype "power_in"))
      (node (ref "IC2") (pin "2") (pinfunction "GND_2") (pintype "power_in"))
      (node (ref "IC7") (pin "2") (pinfunction "GND_2") (pintype "power_in"))
      (node (ref "J1") (pin "10") (pinfunction "10_10") (pintype "bidirectional"))
      (node (ref "J1") (pin "2") (pinfunction "2_2") (pintype "bidirectional"))
      (node (ref "J10") (pin "11") (pinfunction "11_11") (pintype "bidirectional"))
      (node (ref "J10") (pin "7") (pinfunction "7_7") (pintype "bidirectional"))
      (node (ref "J11") (pin "11") (pinfunction "11_11") (pintype "bidirectional"))
      (node (ref "J11") (pin "7") (pinfunction "7_7") (pintype "bidirectional"))
      (node (ref "J4") (pin "1") (pinfunction "1_1") (pintype "bidirectional"))
      (node (ref "J4") (pin "5") (pinfunction "5_5") (pintype "bidirectional"))
      (node (ref "J4") (pin "9") (pinfunction "9_9") (pintype "bidirectional"))
      (node (ref "J9") (pin "1") (pinfunction "1_1") (pintype "bidirectional"))
      (node (ref "J9") (pin "5") (pinfunction "5_5") (pintype "bidirectional"))
      (node (ref "J9") (pin "9") (pinfunction "9_9") (pintype "bidirectional"))
      (node (ref "LD1") (pin "1") (pinfunction "C_1") (pintype "passive"))
      (node (ref "LD26") (pin "1") (pinfunction "C_1") (pintype "passive"))
      (node (ref "LD27") (pin "1") (pinfunction "C_1") (pintype "passive"))
      (node (ref "LD28") (pin "1") (pinfunction "C_1") (pintype "passive"))
      (node (ref "MP1") (pin "1") (pinfunction "1_1") (pintype "passive"))
      (node (ref "MP2") (pin "1") (pinfunction "1_1") (pintype "passive"))
      (node (ref "NT1") (pin "2") (pinfunction "2_2") (pintype "bidirectional"))
      (node (ref "NT10") (pin "2") (pinfunction "2_2") (pintype "bidirectional"))
      (node (ref "NT11") (pin "2") (pinfunction "2_2") (pintype "bidirectional"))
      (node (ref "NT12") (pin "2") (pinfunction "2_2") (pintype "bidirectional"))
      (node (ref "NT13") (pin "2") (pinfunction "2_2") (pintype "bidirectional"))
      (node (ref "NT14") (pin "2") (pinfunction "2_2") (pintype "bidirectional"))
      (node (ref "NT2") (pin "2") (pinfunction "2_2") (pintype "bidirectional"))
      (node (ref "NT3") (pin "2") (pinfunction "2_2") (pintype "bidirectional"))
      (node (ref "NT4") (pin "2") (pinfunction "2_2") (pintype "bidirectional"))
      (node (ref "NT5") (pin "2") (pinfunction "2_2") (pintype "bidirectional"))
      (node (ref "NT6") (pin "2") (pinfunction "2_2") (pintype "bidirectional"))
      (node (ref "NT7") (pin "2") (pinfunction "2_2") (pintype "bidirectional"))
      (node (ref "NT8") (pin "2") (pinfunction "2_2") (pintype "bidirectional"))
      (node (ref "NT9") (pin "2") (pinfunction "2_2") (pintype "bidirectional"))
      (node (ref "SW2") (pin "5") (pinfunction "5_5") (pintype "bidirectional"))
      (node (ref "SW2") (pin "6") (pinfunction "6_6") (pintype "bidirectional"))
      (node (ref "SW2") (pin "7") (pinfunction "7_7") (pintype "bidirectional"))
      (node (ref "SW2") (pin "8") (pinfunction "8_8") (pintype "bidirectional"))
    )
    (net (code "63") (name "Net-(LD1-A)") (class "Default")
      (node (ref "LD1") (pin "2") (pinfunction "A_2") (pintype "passive"))
      (node (ref "R1") (pin "1") (pinfunction "1_1") (pintype "passive"))
    )
    (net (code "64") (name "Net-(LD18-C)") (class "Default")
      (node (ref "LD18") (pin "1") (pinfunction "C_1") (pintype "passive"))
      (node (ref "R26") (pin "1") (pinfunction "1_1") (pintype "passive"))
    )
    (net (code "65") (name "Net-(LD19-C)") (class "Default")
      (node (ref "LD19") (pin "1") (pinfunction "C_1") (pintype "passive"))
      (node (ref "R27") (pin "1") (pinfunction "1_1") (pintype "passive"))
    )
    (net (code "66") (name "Net-(LD20-C)") (class "Default")
      (node (ref "LD20") (pin "1") (pinfunction "C_1") (pintype "passive"))
      (node (ref "R32") (pin "1") (pinfunction "1_1") (pintype "passive"))
    )
    (net (code "67") (name "Net-(LD21-C)") (class "Default")
      (node (ref "LD21") (pin "1") (pinfunction "C_1") (pintype "passive"))
      (node (ref "R33") (pin "1") (pinfunction "1_1") (pintype "passive"))
    )
    (net (code "68") (name "Net-(LD26-A)") (class "Default")
      (node (ref "LD26") (pin "2") (pinfunction "A_2") (pintype "passive"))
      (node (ref "R46") (pin "1") (pinfunction "1_1") (pintype "passive"))
    )
    (net (code "69") (name "Net-(LD27-A)") (class "Default")
      (node (ref "LD27") (pin "2") (pinfunction "A_2") (pintype "passive"))
      (node (ref "R48") (pin "1") (pinfunction "1_1") (pintype "passive"))
    )
    (net (code "70") (name "Net-(LD28-A)") (class "Default")
      (node (ref "LD28") (pin "2") (pinfunction "A_2") (pintype "passive"))
      (node (ref "R2") (pin "2") (pinfunction "2_2") (pintype "passive"))
    )
    (net (code "71") (name "Net-(R47-Pad1)") (class "Default")
      (node (ref "R47") (pin "1") (pinfunction "1_1") (pintype "passive"))
      (node (ref "R48") (pin "2") (pinfunction "2_2") (pintype "passive"))
    )
    (net (code "72") (name "P1V8") (class "Default")
      (node (ref "C232") (pin "2") (pinfunction "2_2") (pintype "passive"))
      (node (ref "C5") (pin "2") (pinfunction "2_2") (pintype "passive"))
      (node (ref "C9") (pin "2") (pinfunction "2_2") (pintype "passive"))
      (node (ref "IC1") (pin "41") (pinfunction "VCCINT_41") (pintype "power_in"))
      (node (ref "IC1") (pin "8") (pinfunction "VCCINT_8") (pintype "power_in"))
      (node (ref "IC2") (pin "5") (pinfunction "VOUT_5") (pintype "power_in"))
    )
    (net (code "73") (name "P3V3") (class "Default")
      (node (ref "C1") (pin "2") (pinfunction "2_2") (pintype "passive"))
      (node (ref "C2") (pin "2") (pinfunction "2_2") (pintype "passive"))
      (node (ref "C3") (pin "2") (pinfunction "2_2") (pintype "passive"))
      (node (ref "C4") (pin "2") (pinfunction "2_2") (pintype "passive"))
      (node (ref "C7") (pin "2") (pinfunction "2_2") (pintype "passive"))
      (node (ref "D1") (pin "1") (pinfunction "C_1") (pintype "passive"))
      (node (ref "IC1") (pin "23") (pinfunction "VCCIO1_23") (pintype "power_in"))
      (node (ref "IC1") (pin "39") (pinfunction "VCCIO2_39") (pintype "power_in"))
      (node (ref "IC1") (pin "57") (pinfunction "VCCIO2_57") (pintype "power_in"))
      (node (ref "IC1") (pin "6") (pinfunction "VCCIO1_6") (pintype "power_in"))
      (node (ref "IC7") (pin "5") (pinfunction "VOUT_5") (pintype "power_in"))
      (node (ref "J1") (pin "4") (pinfunction "4_4") (pintype "bidirectional"))
      (node (ref "LD18") (pin "2") (pinfunction "A_2") (pintype "passive"))
      (node (ref "LD19") (pin "2") (pinfunction "A_2") (pintype "passive"))
      (node (ref "LD20") (pin "2") (pinfunction "A_2") (pintype "passive"))
      (node (ref "LD21") (pin "2") (pinfunction "A_2") (pintype "passive"))
      (node (ref "R46") (pin "2") (pinfunction "2_2") (pintype "passive"))
    )
    (net (code "74") (name "P5V0") (class "Default")
      (node (ref "C231") (pin "2") (pinfunction "2_2") (pintype "passive"))
      (node (ref "C8") (pin "2") (pinfunction "2_2") (pintype "passive"))
      (node (ref "IC2") (pin "1") (pinfunction "VIN_1") (pintype "input"))
      (node (ref "IC2") (pin "3") (pinfunction "EN_3") (pintype "input"))
      (node (ref "IC7") (pin "1") (pinfunction "VIN_1") (pintype "input"))
      (node (ref "IC7") (pin "3") (pinfunction "EN_3") (pintype "input"))
      (node (ref "J10") (pin "2") (pinfunction "2_2") (pintype "bidirectional"))
      (node (ref "J11") (pin "2") (pinfunction "2_2") (pintype "bidirectional"))
      (node (ref "R47") (pin "2") (pinfunction "2_2") (pintype "passive"))
    )
    (net (code "75") (name "P12V0") (class "Default")
      (node (ref "J10") (pin "1") (pinfunction "1_1") (pintype "bidirectional"))
      (node (ref "J10") (pin "3") (pinfunction "3_3") (pintype "bidirectional"))
      (node (ref "J11") (pin "1") (pinfunction "1_1") (pintype "bidirectional"))
      (node (ref "J11") (pin "3") (pinfunction "3_3") (pintype "bidirectional"))
      (node (ref "R2") (pin "1") (pinfunction "1_1") (pintype "passive"))
    )
    (net (code "76") (name "unconnected-(IC2-NC-Pad4)") (class "Default")
      (node (ref "IC2") (pin "4") (pinfunction "NC_4") (pintype "passive"))
    )
    (net (code "77") (name "unconnected-(IC7-NC-Pad4)") (class "Default")
      (node (ref "IC7") (pin "4") (pinfunction "NC_4") (pintype "passive"))
    )
    (net (code "78") (name "unconnected-(J1-Pad6)") (class "Default")
      (node (ref "J1") (pin "6") (pinfunction "6_6") (pintype "bidirectional"))
    )
    (net (code "79") (name "unconnected-(J1-Pad7)") (class "Default")
      (node (ref "J1") (pin "7") (pinfunction "7_7") (pintype "bidirectional"))
    )
    (net (code "80") (name "unconnected-(J1-Pad8)") (class "Default")
      (node (ref "J1") (pin "8") (pinfunction "8_8") (pintype "bidirectional"))
    )
  )
)
